# 04_Power_Supplies.net
KiCad netlist of a schematic drawn in Altium Designer
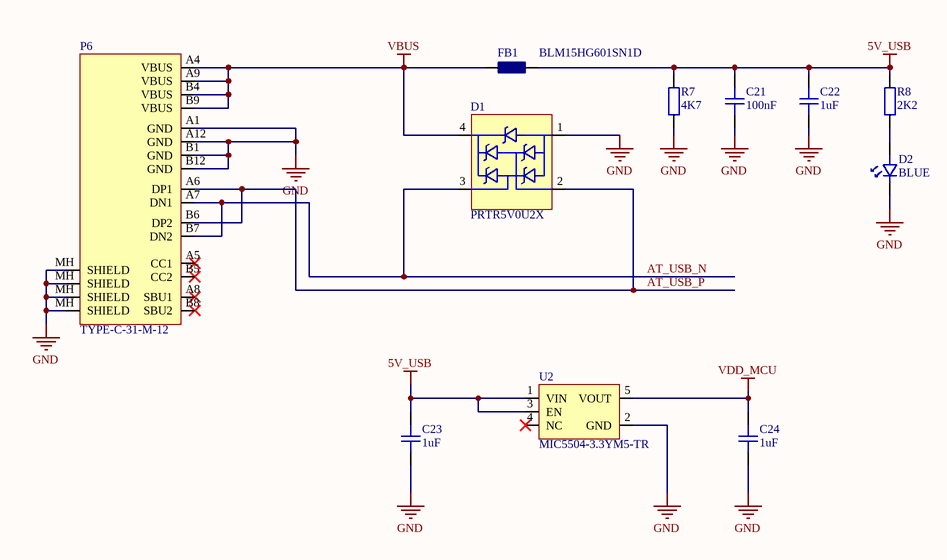
[diagram p0: [04]Power Supplies.SchDoc]

(export (version "E")
  (design (tool "Eeschema 10.0.6"))
  (components
    (comp (ref "C21")
      (value "100nF")
      (footprint "CAPC1005L")
      (description "Surface Mount Unpolarized Capacitor")
      (libsource (lib "Discrete") (part "CAP_CHP"))
    )
    (comp (ref "C22")
      (value "1uF")
      (footprint "CAPC1005L")
      (description "Surface Mount Unpolarized Capacitor")
      (libsource (lib "Discrete") (part "CAP_CHP"))
    )
    (comp (ref "C23")
      (value "1uF")
      (footprint "CAPC1005L")
      (description "Surface Mount Unpolarized Capacitor")
      (libsource (lib "Discrete") (part "CAP_CHP"))
    )
    (comp (ref "C24")
      (value "1uF")
      (footprint "CAPC1005L")
      (description "Surface Mount Unpolarized Capacitor")
      (libsource (lib "Discrete") (part "CAP_CHP"))
    )
    (comp (ref "D1")
      (value "PRTR5V0U2X")
      (footprint "SOT143L")
      (description "Ultra low capacitance double rail-to-rail ESD protection diode")
      (libsource (lib "Discrete") (part "PRTR5V0U2X"))
    )
    (comp (ref "D2")
      (value "BLUE")
      (footprint "LEDC1608L")
      (description "Surface Mount LED")
      (libsource (lib "Discrete") (part "LED_SMD"))
    )
    (comp (ref "FB1")
      (value "BLM15HG601SN1D")
      (footprint "FBDC1005L")
      (description "Surface Mount Ferrite Bead")
      (libsource (lib "Discrete") (part "FBD_CHP"))
    )
    (comp (ref "P6")
      (value "TYPE-C-31-M-12")
      (footprint "TYPE-C-31-M-12")
      (description "USB Type-C Connector")
      (libsource (lib "AmbiqPhoenix") (part "TYPE-C-31-M-12"))
    )
    (comp (ref "R7")
      (value "4K7")
      (footprint "RESC1005L")
      (description "Surface Mount Resistor")
      (libsource (lib "Discrete") (part "RES_CHP"))
    )
    (comp (ref "R8")
      (value "2K2")
      (footprint "RESC1005L")
      (description "Surface Mount Resistor")
      (libsource (lib "Discrete") (part "RES_CHP"))
    )
    (comp (ref "U2")
      (value "MIC5504-3.3YM5-TR")
      (footprint "SOT23-5_L")
      (description "Linear Voltage Regulator Positive Fixed 1 Output 3.3V 300mA SOT-23-5")
      (libsource (lib "IC") (part "MIC5504-3.3YM5-TR"))
    )
  )
  (nets
    (net (code "1") (name "/AT_USB_N") (class "Default")
      (node (ref "D1") (pin "3") (pinfunction "3_3") (pintype "passive"))
      (node (ref "P6") (pin "A7") (pinfunction "DN1_A7") (pintype "passive"))
      (node (ref "P6") (pin "B7") (pinfunction "DN2_B7") (pintype "passive"))
    )
    (net (code "2") (name "/AT_USB_P") (class "Default")
      (node (ref "D1") (pin "2") (pinfunction "2_2") (pintype "passive"))
      (node (ref "P6") (pin "A6") (pinfunction "DP1_A6") (pintype "passive"))
      (node (ref "P6") (pin "B6") (pinfunction "DP2_B6") (pintype "passive"))
    )
    (net (code "3") (name "5V_USB") (class "Default")
      (node (ref "C21") (pin "2") (pinfunction "2_2") (pintype "passive"))
      (node (ref "C22") (pin "2") (pinfunction "2_2") (pintype "passive"))
      (node (ref "C23") (pin "2") (pinfunction "2_2") (pintype "passive"))
      (node (ref "FB1") (pin "2") (pinfunction "2_2") (pintype "passive"))
      (node (ref "R7") (pin "2") (pinfunction "2_2") (pintype "passive"))
      (node (ref "R8") (pin "1") (pinfunction "1_1") (pintype "passive"))
      (node (ref "U2") (pin "1") (pinfunction "VIN_1") (pintype "passive"))
      (node (ref "U2") (pin "3") (pinfunction "EN_3") (pintype "passive"))
    )
    (net (code "4") (name "GND") (class "Default")
      (node (ref "C21") (pin "1") (pinfunction "1_1") (pintype "passive"))
      (node (ref "C22") (pin "1") (pinfunction "1_1") (pintype "passive"))
      (node (ref "C23") (pin "1") (pinfunction "1_1") (pintype "passive"))
      (node (ref "C24") (pin "1") (pinfunction "1_1") (pintype "passive"))
      (node (ref "D1") (pin "1") (pinfunction "1_1") (pintype "passive"))
      (node (ref "D2") (pin "1") (pinfunction "1_1") (pintype "passive"))
      (node (ref "P6") (pin "A1") (pinfunction "GND_A1") (pintype "passive"))
      (node (ref "P6") (pin "A12") (pinfunction "GND_A12") (pintype "passive"))
      (node (ref "P6") (pin "B1") (pinfunction "GND_B1") (pintype "passive"))
      (node (ref "P6") (pin "B12") (pinfunction "GND_B12") (pintype "passive"))
      (node (ref "P6") (pin "MH") (pinfunction "SHIELD_MH") (pintype "passive"))
      (node (ref "R7") (pin "1") (pinfunction "1_1") (pintype "passive"))
      (node (ref "U2") (pin "2") (pinfunction "GND_2") (pintype "passive"))
    )
    (net (code "5") (name "Net-(D2-Pad2)") (class "Default")
      (node (ref "D2") (pin "2") (pinfunction "2_2") (pintype "passive"))
      (node (ref "R8") (pin "2") (pinfunction "2_2") (pintype "passive"))
    )
    (net (code "6") (name "VBUS") (class "Default")
      (node (ref "D1") (pin "4") (pinfunction "4_4") (pintype "passive"))
      (node (ref "FB1") (pin "1") (pinfunction "1_1") (pintype "passive"))
      (node (ref "P6") (pin "A4") (pinfunction "VBUS_A4") (pintype "passive"))
      (node (ref "P6") (pin "A9") (pinfunction "VBUS_A9") (pintype "passive"))
      (node (ref "P6") (pin "B4") (pinfunction "VBUS_B4") (pintype "passive"))
      (node (ref "P6") (pin "B9") (pinfunction "VBUS_B9") (pintype "passive"))
    )
    (net (code "7") (name "VDD_MCU") (class "Default")
      (node (ref "C24") (pin "2") (pinfunction "2_2") (pintype "passive"))
      (node (ref "U2") (pin "5") (pinfunction "VOUT_5") (pintype "passive"))
    )
    (net (code "8") (name "unconnected-(P6-CC1-PadA5)") (class "Default")
      (node (ref "P6") (pin "A5") (pinfunction "CC1_A5") (pintype "passive+no_connect"))
    )
    (net (code "9") (name "unconnected-(P6-CC2-PadB5)") (class "Default")
      (node (ref "P6") (pin "B5") (pinfunction "CC2_B5") (pintype "passive+no_connect"))
    )
    (net (code "10") (name "unconnected-(P6-SBU1-PadA8)") (class "Default")
      (node (ref "P6") (pin "A8") (pinfunction "SBU1_A8") (pintype "passive+no_connect"))
    )
    (net (code "11") (name "unconnected-(P6-SBU2-PadB8)") (class "Default")
      (node (ref "P6") (pin "B8") (pinfunction "SBU2_B8") (pintype "passive+no_connect"))
    )
    (net (code "12") (name "unconnected-(U2-NC-Pad4)") (class "Default")
      (node (ref "U2") (pin "4") (pinfunction "NC_4") (pintype "passive+no_connect"))
    )
  )
)
